# Main.net
KiCad netlist of a schematic drawn in Altium Designer
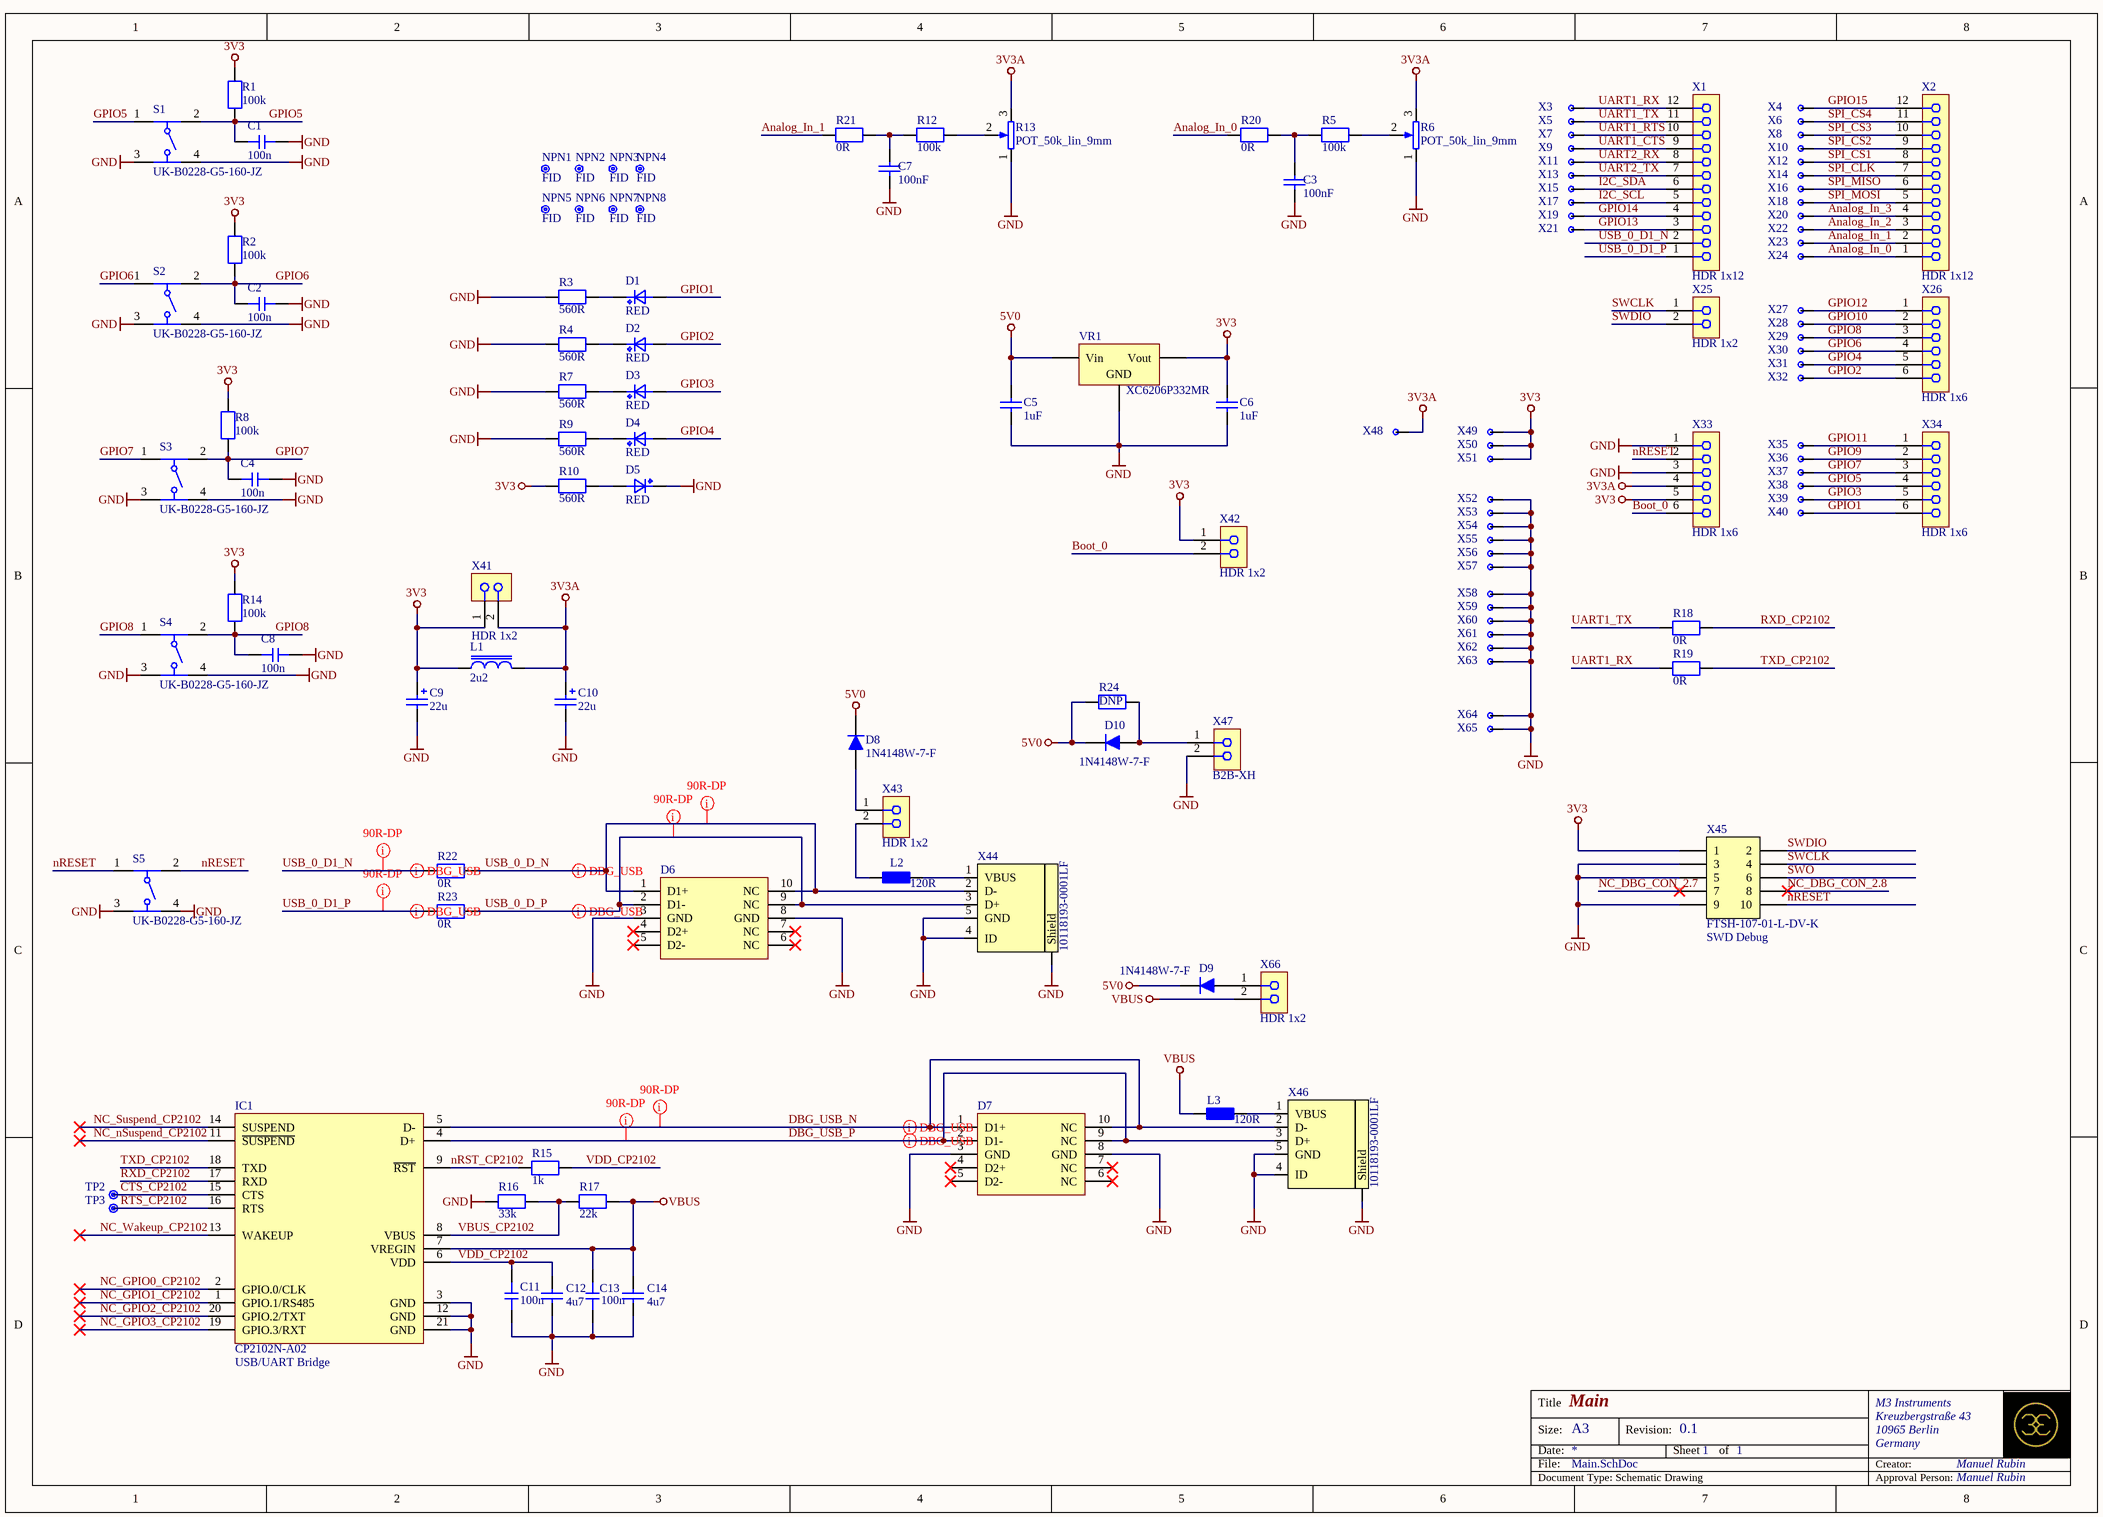
[diagram p0: Main.SchDoc]

(export (version "E")
  (design (tool "Eeschema 10.0.6"))
  (components
    (comp (ref "C1")
      (value "100n")
      (footprint "CAPC1608X95N")
      (description "100n_50V")
      (fields (field (name "MANUFACTURER") "AVX") (field (name "MANUFACTURER PART NUMBER") "06031C104KAT2A"))
      (libsource (lib "Raindancer") (part "C_100n_50V_0603"))
    )
    (comp (ref "C2")
      (value "100n")
      (footprint "CAPC1608X95N")
      (description "100n_50V")
      (fields (field (name "MANUFACTURER") "AVX") (field (name "MANUFACTURER PART NUMBER") "06031C104KAT2A"))
      (libsource (lib "Raindancer") (part "C_100n_50V_0603"))
    )
    (comp (ref "C3")
      (value "100nF")
      (footprint "CAPC1608X95N")
      (description "Multilayer Ceramic Capacitors MLCC - SMD/SMT, 100nF")
      (fields
        (field (name "MANUFACTURER") "YAGEO")
        (field (name "MANUFACTURER PART NUMBER") "CC0603KRX7R9BB104")
      )
      (libsource (lib "Caps") (part "CAP_100nF_0603"))
    )
    (comp (ref "C4")
      (value "100n")
      (footprint "CAPC1608X95N")
      (description "100n_50V")
      (fields (field (name "MANUFACTURER") "AVX") (field (name "MANUFACTURER PART NUMBER") "06031C104KAT2A"))
      (libsource (lib "Raindancer") (part "C_100n_50V_0603"))
    )
    (comp (ref "C5")
      (value "1uF")
      (footprint "CAPC2012X145N")
      (description "Multilayer Ceramic Capacitors MLCC - SMD/SMT, 1uF")
      (fields (field (name "MANUFACTURER") "Samsung Electro-Mechanics") (field (name "TOLERANCE") "10%"))
      (libsource (lib "Caps") (part "CAP_1uF_0805"))
    )
    (comp (ref "C6")
      (value "1uF")
      (footprint "CAPC2012X145N")
      (description "Multilayer Ceramic Capacitors MLCC - SMD/SMT, 1uF")
      (fields (field (name "MANUFACTURER") "Samsung Electro-Mechanics") (field (name "TOLERANCE") "10%"))
      (libsource (lib "Caps") (part "CAP_1uF_0805"))
    )
    (comp (ref "C7")
      (value "100nF")
      (footprint "CAPC1608X95N")
      (description "Multilayer Ceramic Capacitors MLCC - SMD/SMT, 100nF")
      (fields
        (field (name "MANUFACTURER") "YAGEO")
        (field (name "MANUFACTURER PART NUMBER") "CC0603KRX7R9BB104")
      )
      (libsource (lib "Caps") (part "CAP_100nF_0603"))
    )
    (comp (ref "C8")
      (value "100n")
      (footprint "CAPC1608X95N")
      (description "100n_50V")
      (fields (field (name "MANUFACTURER") "AVX") (field (name "MANUFACTURER PART NUMBER") "06031C104KAT2A"))
      (libsource (lib "Raindancer") (part "C_100n_50V_0603"))
    )
    (comp (ref "C9")
      (value "22u")
      (footprint "CAPAE4643X54M")
      (description "Aluminium Electrolytic Capacitors - SMD 22UF 16V HA SMD")
      (fields
        (field (name "MANUFACTURER") "Panasonic")
        (field (name "MANUFACTURER PART NUMBER") "EEE-HAC220WAR")
      )
      (libsource (lib "Caps") (part "CAP_22u"))
    )
    (comp (ref "C10")
      (value "22u")
      (footprint "CAPAE4643X54M")
      (description "Aluminium Electrolytic Capacitors - SMD 22UF 16V HA SMD")
      (fields
        (field (name "MANUFACTURER") "Panasonic")
        (field (name "MANUFACTURER PART NUMBER") "EEE-HAC220WAR")
      )
      (libsource (lib "Caps") (part "CAP_22u"))
    )
    (comp (ref "C11")
      (value "100n")
      (footprint "CAPC1608X95N")
      (description "100n_50V")
      (fields (field (name "MANUFACTURER") "AVX") (field (name "MANUFACTURER PART NUMBER") "06031C104KAT2A"))
      (libsource (lib "Raindancer") (part "C_100n_50V_0603"))
    )
    (comp (ref "C12")
      (value "4u7")
      (footprint "CAPC1608X95N")
      (description "16V 4.7uF X5R ±10% 0603 Multilayer Ceramic Capacitors MLCC - SMD/SMT ROHS")
      (fields
        (field (name "MANUFACTURER") "Murata Electronics")
        (field (name "MANUFACTURER PART NUMBER") "GRM188C81C475KE11D")
      )
      (libsource (lib "Caps") (part "CAP_4u7_0603"))
    )
    (comp (ref "C13")
      (value "100n")
      (footprint "CAPC1608X95N")
      (description "100n_50V")
      (fields (field (name "MANUFACTURER") "AVX") (field (name "MANUFACTURER PART NUMBER") "06031C104KAT2A"))
      (libsource (lib "Raindancer") (part "C_100n_50V_0603"))
    )
    (comp (ref "C14")
      (value "4u7")
      (footprint "CAPC1608X95N")
      (description "16V 4.7uF X5R ±10% 0603 Multilayer Ceramic Capacitors MLCC - SMD/SMT ROHS")
      (fields
        (field (name "MANUFACTURER") "Murata Electronics")
        (field (name "MANUFACTURER PART NUMBER") "GRM188C81C475KE11D")
      )
      (libsource (lib "Caps") (part "CAP_4u7_0603"))
    )
    (comp (ref "D1")
      (value "RED")
      (footprint "WL-SMCW_0805")
      (description "Standard LEDs - SMD WL-SMCW SMDMono TpVw Waterclr 0805 Red")
      (fields
        (field (name "MANUFACTURER") "Wurth Elektronik")
        (field (name "MANUFACTURER PART NUMBER") "150080RS75000")
      )
      (libsource (lib "Diodes") (part "LED_0805_RED_AK"))
    )
    (comp (ref "D2")
      (value "RED")
      (footprint "WL-SMCW_0805")
      (description "Standard LEDs - SMD WL-SMCW SMDMono TpVw Waterclr 0805 Red")
      (fields
        (field (name "MANUFACTURER") "Wurth Elektronik")
        (field (name "MANUFACTURER PART NUMBER") "150080RS75000")
      )
      (libsource (lib "Diodes") (part "LED_0805_RED_AK"))
    )
    (comp (ref "D3")
      (value "RED")
      (footprint "WL-SMCW_0805")
      (description "Standard LEDs - SMD WL-SMCW SMDMono TpVw Waterclr 0805 Red")
      (fields
        (field (name "MANUFACTURER") "Wurth Elektronik")
        (field (name "MANUFACTURER PART NUMBER") "150080RS75000")
      )
      (libsource (lib "Diodes") (part "LED_0805_RED_AK"))
    )
    (comp (ref "D4")
      (value "RED")
      (footprint "WL-SMCW_0805")
      (description "Standard LEDs - SMD WL-SMCW SMDMono TpVw Waterclr 0805 Red")
      (fields
        (field (name "MANUFACTURER") "Wurth Elektronik")
        (field (name "MANUFACTURER PART NUMBER") "150080RS75000")
      )
      (libsource (lib "Diodes") (part "LED_0805_RED_AK"))
    )
    (comp (ref "D5")
      (value "RED")
      (footprint "WL-SMCW_0805")
      (description "Standard LEDs - SMD WL-SMCW SMDMono TpVw Waterclr 0805 Red")
      (fields
        (field (name "MANUFACTURER") "Wurth Elektronik")
        (field (name "MANUFACTURER PART NUMBER") "150080RS75000")
      )
      (libsource (lib "Diodes") (part "LED_0805_RED_AK"))
    )
    (comp (ref "D6")
      (value "~")
      (footprint "DQA R-PUSON-N10")
      (description "2-, 4-Channel ESD Protection for Super-Speed USB 3.0 Interface")
      (fields
        (field (name "MANUFACTURER") "Texas Instruments")
        (field (name "MANUFACTURER PART NUMBER") "TPD4EUSB30DQAR")
      )
      (libsource (lib "Diodes") (part "TPD4EUSB30DQAR"))
    )
    (comp (ref "D7")
      (value "~")
      (footprint "DQA R-PUSON-N10")
      (description "2-, 4-Channel ESD Protection for Super-Speed USB 3.0 Interface")
      (fields
        (field (name "MANUFACTURER") "Texas Instruments")
        (field (name "MANUFACTURER PART NUMBER") "TPD4EUSB30DQAR")
      )
      (libsource (lib "Diodes") (part "TPD4EUSB30DQAR"))
    )
    (comp (ref "D8")
      (value "1N4148W-7-F")
      (footprint "SOD-123")
      (description "Diodes - General Purpose, Power, Switching SURFACE MOUNT FAST SWITCHING DIODE 2A")
      (fields (field (name "MANUFACTURER") "Diodes Incorporated"))
      (libsource (lib "Diodes") (part "1N4148W-7-F"))
    )
    (comp (ref "D9")
      (value "1N4148W-7-F")
      (footprint "SOD-123")
      (description "Diodes - General Purpose, Power, Switching SURFACE MOUNT FAST SWITCHING DIODE 2A")
      (fields (field (name "MANUFACTURER") "Diodes Incorporated"))
      (libsource (lib "Diodes") (part "1N4148W-7-F"))
    )
    (comp (ref "D10")
      (value "1N4148W-7-F")
      (footprint "SOD-123")
      (description "Diodes - General Purpose, Power, Switching SURFACE MOUNT FAST SWITCHING DIODE 2A")
      (fields (field (name "MANUFACTURER") "Diodes Incorporated"))
      (libsource (lib "Diodes") (part "1N4148W-7-F"))
    )
    (comp (ref "IC1")
      (value "CP2102N-A02")
      (footprint "SILABS_CP2102N-A02-GQFN20R")
      (description "USB Interface IC USBXpress - USB to UART Bridge QFN28")
      (fields
        (field (name "MANUFACTURER") "Silicon Labs")
        (field (name "MANUFACTURER PART NUMBER") "CP2102N-A02-GQFN20R")
        (field (name "DEVNOTE") "USB/UART Bridge")
      )
      (libsource (lib "Raindancer") (part "IC_CP2102N-A02-QFN20"))
    )
    (comp (ref "L1")
      (value "2u2")
      (footprint "INDP5050X39N")
      (description "Fixed Inductors 2.2uH 3.8A")
      (fields
        (field (name "MANUFACTURER") "Bourns")
        (field (name "MANUFACTURER PART NUMBER") "SRN5040TA-2R2M")
      )
      (libsource (lib "Inductors") (part "IND_2u2_3.8A"))
    )
    (comp (ref "L2")
      (value "120R")
      (footprint "INDC1608X95AN")
      (description "Chip Bead Inductors for Power Lines")
      (fields
        (field (name "MANUFACTURER") "Taiyo Yuden")
        (field (name "MANUFACTURER PART NUMBER") "FBMH1608HL121-T")
      )
      (libsource (lib "Inductors") (part "FB_600R_0603"))
    )
    (comp (ref "L3")
      (value "120R")
      (footprint "INDC1608X95AN")
      (description "Chip Bead Inductors for Power Lines")
      (fields
        (field (name "MANUFACTURER") "Taiyo Yuden")
        (field (name "MANUFACTURER PART NUMBER") "FBMH1608HL121-T")
      )
      (libsource (lib "Inductors") (part "FB_600R_0603"))
    )
    (comp (ref "NPN1")
      (value "FID")
      (footprint "Fiducial_1mm")
      (libsource (lib "MISC") (part "Fiducial_1mm"))
    )
    (comp (ref "NPN2")
      (value "FID")
      (footprint "Fiducial_1mm")
      (libsource (lib "MISC") (part "Fiducial_1mm"))
    )
    (comp (ref "NPN3")
      (value "FID")
      (footprint "Fiducial_1mm")
      (libsource (lib "MISC") (part "Fiducial_1mm"))
    )
    (comp (ref "NPN4")
      (value "FID")
      (footprint "Fiducial_1mm")
      (libsource (lib "MISC") (part "Fiducial_1mm"))
    )
    (comp (ref "NPN5")
      (value "FID")
      (footprint "Fiducial_1mm")
      (libsource (lib "MISC") (part "Fiducial_1mm"))
    )
    (comp (ref "NPN6")
      (value "FID")
      (footprint "Fiducial_1mm")
      (libsource (lib "MISC") (part "Fiducial_1mm"))
    )
    (comp (ref "NPN7")
      (value "FID")
      (footprint "Fiducial_1mm")
      (libsource (lib "MISC") (part "Fiducial_1mm"))
    )
    (comp (ref "NPN8")
      (value "FID")
      (footprint "Fiducial_1mm")
      (libsource (lib "MISC") (part "Fiducial_1mm"))
    )
    (comp (ref "R1")
      (value "100k")
      (footprint "RESC2012X70N")
      (description "Thick Film Resistors - SMD 1/8watt 100Kohms 1% 100ppm")
      (fields
        (field (name "MANUFACTURER") "Vishay / Dale")
        (field (name "MANUFACTURER PART NUMBER") "CRCW0805100KFKEA")
      )
      (libsource (lib "Resistors") (part "RES_100k_0805"))
    )
    (comp (ref "R2")
      (value "100k")
      (footprint "RESC2012X70N")
      (description "Thick Film Resistors - SMD 1/8watt 100Kohms 1% 100ppm")
      (fields
        (field (name "MANUFACTURER") "Vishay / Dale")
        (field (name "MANUFACTURER PART NUMBER") "CRCW0805100KFKEA")
      )
      (libsource (lib "Resistors") (part "RES_100k_0805"))
    )
    (comp (ref "R3")
      (value "560R")
      (footprint "RESC1608X55N")
      (description "Thick Film Resistors - SMD 560 Ohms 125 mW 0603")
      (fields
        (field (name "MANUFACTURER") "ROHM Semicon")
        (field (name "MANUFACTURER PART NUMBER") "MCR03ERTF5600")
      )
      (libsource (lib "Resistors") (part "RES_560R_0603"))
    )
    (comp (ref "R4")
      (value "560R")
      (footprint "RESC1608X55N")
      (description "Thick Film Resistors - SMD 560 Ohms 125 mW 0603")
      (fields
        (field (name "MANUFACTURER") "ROHM Semicon")
        (field (name "MANUFACTURER PART NUMBER") "MCR03ERTF5600")
      )
      (libsource (lib "Resistors") (part "RES_560R_0603"))
    )
    (comp (ref "R5")
      (value "100k")
      (footprint "RESC2012X70N")
      (description "Thick Film Resistors - SMD 1/8watt 100Kohms 1% 100ppm")
      (fields
        (field (name "MANUFACTURER") "Vishay / Dale")
        (field (name "MANUFACTURER PART NUMBER") "CRCW0805100KFKEA")
      )
      (libsource (lib "") (part "RES_100k_0805_1"))
    )
    (comp (ref "R6")
      (value "POT_50k_lin_9mm")
      (footprint "PTV09")
      (description "PTV09A-4020F-A203 50k, 20mm")
      (fields
        (field (name "MANUFACTURER") "Bourns")
        (field (name "MANUFACTURER PART NUMBER") "PTV09A-5020F-A503")
      )
      (libsource (lib "Resistors") (part "POT_50k_lin_9mm"))
    )
    (comp (ref "R7")
      (value "560R")
      (footprint "RESC1608X55N")
      (description "Thick Film Resistors - SMD 560 Ohms 125 mW 0603")
      (fields
        (field (name "MANUFACTURER") "ROHM Semicon")
        (field (name "MANUFACTURER PART NUMBER") "MCR03ERTF5600")
      )
      (libsource (lib "Resistors") (part "RES_560R_0603"))
    )
    (comp (ref "R8")
      (value "100k")
      (footprint "RESC2012X70N")
      (description "Thick Film Resistors - SMD 1/8watt 100Kohms 1% 100ppm")
      (fields
        (field (name "MANUFACTURER") "Vishay / Dale")
        (field (name "MANUFACTURER PART NUMBER") "CRCW0805100KFKEA")
      )
      (libsource (lib "Resistors") (part "RES_100k_0805"))
    )
    (comp (ref "R9")
      (value "560R")
      (footprint "RESC1608X55N")
      (description "Thick Film Resistors - SMD 560 Ohms 125 mW 0603")
      (fields
        (field (name "MANUFACTURER") "ROHM Semicon")
        (field (name "MANUFACTURER PART NUMBER") "MCR03ERTF5600")
      )
      (libsource (lib "Resistors") (part "RES_560R_0603"))
    )
    (comp (ref "R10")
      (value "560R")
      (footprint "RESC1608X55N")
      (description "Thick Film Resistors - SMD 560 Ohms 125 mW 0603")
      (fields
        (field (name "MANUFACTURER") "ROHM Semicon")
        (field (name "MANUFACTURER PART NUMBER") "MCR03ERTF5600")
      )
      (libsource (lib "Resistors") (part "RES_560R_0603"))
    )
    (comp (ref "R12")
      (value "100k")
      (footprint "RESC2012X70N")
      (description "Thick Film Resistors - SMD 1/8watt 100Kohms 1% 100ppm")
      (fields
        (field (name "MANUFACTURER") "Vishay / Dale")
        (field (name "MANUFACTURER PART NUMBER") "CRCW0805100KFKEA")
      )
      (libsource (lib "") (part "RES_100k_0805_1"))
    )
    (comp (ref "R13")
      (value "POT_50k_lin_9mm")
      (footprint "PTV09")
      (description "PTV09A-4020F-A203 50k, 20mm")
      (fields
        (field (name "MANUFACTURER") "Bourns")
        (field (name "MANUFACTURER PART NUMBER") "PTV09A-5020F-A503")
      )
      (libsource (lib "Resistors") (part "POT_50k_lin_9mm"))
    )
    (comp (ref "R14")
      (value "100k")
      (footprint "RESC2012X70N")
      (description "Thick Film Resistors - SMD 1/8watt 100Kohms 1% 100ppm")
      (fields
        (field (name "MANUFACTURER") "Vishay / Dale")
        (field (name "MANUFACTURER PART NUMBER") "CRCW0805100KFKEA")
      )
      (libsource (lib "Resistors") (part "RES_100k_0805"))
    )
    (comp (ref "R15")
      (value "1k")
      (footprint "RESC1608X55AN")
      (description "Thick Film Resistors - SMD 1 kOhms 100mW 0603 1%")
      (fields
        (field (name "MANUFACTURER") "Yageo")
        (field (name "MANUFACTURER PART NUMBER") "RC0603FR-071KL")
      )
      (libsource (lib "Raindancer") (part "RES_1k_0603"))
    )
    (comp (ref "R16")
      (value "33k")
      (footprint "RESC1608X55AN")
      (description "Thick Film Resistors - SMD 33 kOhms 100 mW 0603 5%")
      (fields
        (field (name "MANUFACTURER") "YAGEO")
        (field (name "MANUFACTURER PART NUMBER") "RC0603JR-0733KL")
      )
      (libsource (lib "Raindancer") (part "RES_33k_0603"))
    )
    (comp (ref "R17")
      (value "22k")
      (footprint "RESC1608X55AN")
      (description "Thick Film Resistors - SMD 22kOhms 1/10W 0603 1%")
      (fields
        (field (name "MANUFACTURER") "YAGEO")
        (field (name "MANUFACTURER PART NUMBER") "RC0603FR-7W22KL")
      )
      (libsource (lib "Raindancer") (part "RES_22k_0603"))
    )
    (comp (ref "R18")
      (value "0R")
      (footprint "RESC1608X55N")
      (description "Thick Film Resistors - SMD 1/10watt ZEROohm Jumper")
      (fields
        (field (name "MANUFACTURER") "Vishay")
        (field (name "MANUFACTURER PART NUMBER") "CRCW06030000Z0EA")
      )
      (libsource (lib "Resistors") (part "RES_0R_0603"))
    )
    (comp (ref "R19")
      (value "0R")
      (footprint "RESC1608X55N")
      (description "Thick Film Resistors - SMD 1/10watt ZEROohm Jumper")
      (fields
        (field (name "MANUFACTURER") "Vishay")
        (field (name "MANUFACTURER PART NUMBER") "CRCW06030000Z0EA")
      )
      (libsource (lib "Resistors") (part "RES_0R_0603"))
    )
    (comp (ref "R20")
      (value "0R")
      (footprint "RESC1608X55N")
      (description "Thick Film Resistors - SMD 1/10watt ZEROohm Jumper")
      (fields
        (field (name "MANUFACTURER") "Vishay")
        (field (name "MANUFACTURER PART NUMBER") "CRCW06030000Z0EA")
      )
      (libsource (lib "Resistors") (part "RES_0R_0603"))
    )
    (comp (ref "R21")
      (value "0R")
      (footprint "RESC1608X55N")
      (description "Thick Film Resistors - SMD 1/10watt ZEROohm Jumper")
      (fields
        (field (name "MANUFACTURER") "Vishay")
        (field (name "MANUFACTURER PART NUMBER") "CRCW06030000Z0EA")
      )
      (libsource (lib "Resistors") (part "RES_0R_0603"))
    )
    (comp (ref "R22")
      (value "0R")
      (footprint "RESC1608X55N")
      (description "Thick Film Resistors - SMD 1/10watt ZEROohm Jumper")
      (fields
        (field (name "MANUFACTURER") "Vishay")
        (field (name "MANUFACTURER PART NUMBER") "CRCW06030000Z0EA")
      )
      (libsource (lib "Resistors") (part "RES_0R_0603"))
    )
    (comp (ref "R23")
      (value "0R")
      (footprint "RESC1608X55N")
      (description "Thick Film Resistors - SMD 1/10watt ZEROohm Jumper")
      (fields
        (field (name "MANUFACTURER") "Vishay")
        (field (name "MANUFACTURER PART NUMBER") "CRCW06030000Z0EA")
      )
      (libsource (lib "Resistors") (part "RES_0R_0603"))
    )
    (comp (ref "R24")
      (value "DNP")
      (footprint "RESC2012X70N")
      (description "Resistor SMD 0805 - not populated")
      (libsource (lib "Resistors") (part "RES_DNF_0805"))
    )
    (comp (ref "S1")
      (value "UK-B0228-G5-160-JZ")
      (footprint "UK-B0228-G5-160-JZ")
      (fields (field (name "MANUFACTURER") "USAKRO"))
      (libsource (lib "Switches") (part "SW_UK-B0228-G5-160-JZ"))
    )
    (comp (ref "S2")
      (value "UK-B0228-G5-160-JZ")
      (footprint "UK-B0228-G5-160-JZ")
      (fields (field (name "MANUFACTURER") "USAKRO"))
      (libsource (lib "Switches") (part "SW_UK-B0228-G5-160-JZ"))
    )
    (comp (ref "S3")
      (value "UK-B0228-G5-160-JZ")
      (footprint "UK-B0228-G5-160-JZ")
      (fields (field (name "MANUFACTURER") "USAKRO"))
      (libsource (lib "Switches") (part "SW_UK-B0228-G5-160-JZ"))
    )
    (comp (ref "S4")
      (value "UK-B0228-G5-160-JZ")
      (footprint "UK-B0228-G5-160-JZ")
      (fields (field (name "MANUFACTURER") "USAKRO"))
      (libsource (lib "Switches") (part "SW_UK-B0228-G5-160-JZ"))
    )
    (comp (ref "S5")
      (value "UK-B0228-G5-160-JZ")
      (footprint "UK-B0228-G5-160-JZ")
      (fields (field (name "MANUFACTURER") "USAKRO"))
      (libsource (lib "Switches") (part "SW_UK-B0228-G5-160-JZ"))
    )
    (comp (ref "TP2")
      (value "TP 0.7mm")
      (footprint "TP_0.7mm")
      (description "Test Pad surface mount")
      (libsource (lib "Raindancer") (part "MISC_Test Pad 0.7mm"))
    )
    (comp (ref "TP3")
      (value "TP 0.7mm")
      (footprint "TP_0.7mm")
      (description "Test Pad surface mount")
      (libsource (lib "Raindancer") (part "MISC_Test Pad 0.7mm"))
    )
    (comp (ref "VR1")
      (value "XC6206P332MR")
      (footprint "SOT95P280X135-3N_123")
      (description "LOW DROPOUT REGULATORS(LDO) POSITIVE FIXED 680MV @ 100MA 6V 3.3V 200MA SOT-23-3L ROHS")
      (fields (field (name "MANUFACTURER") "Torex Semicon"))
      (libsource (lib "ICs") (part "IC_XC6206P332MR"))
    )
    (comp (ref "X1")
      (value "HDR 1x12")
      (footprint "61301211821_NO")
      (description "Board-to-Board-Steckverbinder, 2.54 mm, 12 Kontakt(e), Stiftleiste 1-Reihig")
      (fields (field (name "MANUFACTURER") "WE") (field (name "MANUFACTURER PART NUMBER") "61301211821"))
      (libsource (lib "Connectors") (part "CON_HEADER_1X12_FEMALE_NO"))
    )
    (comp (ref "X2")
      (value "HDR 1x12")
      (footprint "61301211821_NO")
      (description "Board-to-Board-Steckverbinder, 2.54 mm, 12 Kontakt(e), Stiftleiste 1-Reihig")
      (fields (field (name "MANUFACTURER") "WE") (field (name "MANUFACTURER PART NUMBER") "61301211821"))
      (libsource (lib "Connectors") (part "CON_HEADER_1X12_FEMALE_NO"))
    )
    (comp (ref "X3") (value "PAD") (footprint "PAD_1.1_1.6") (libsource (lib "MISC") (part "PAD_2.54")))
    (comp (ref "X4") (value "PAD") (footprint "PAD_1.1_1.6") (libsource (lib "MISC") (part "PAD_2.54")))
    (comp (ref "X5") (value "PAD") (footprint "PAD_1.1_1.6") (libsource (lib "MISC") (part "PAD_2.54")))
    (comp (ref "X6") (value "PAD") (footprint "PAD_1.1_1.6") (libsource (lib "MISC") (part "PAD_2.54")))
    (comp (ref "X7") (value "PAD") (footprint "PAD_1.1_1.6") (libsource (lib "MISC") (part "PAD_2.54")))
    (comp (ref "X8") (value "PAD") (footprint "PAD_1.1_1.6") (libsource (lib "MISC") (part "PAD_2.54")))
    (comp (ref "X9") (value "PAD") (footprint "PAD_1.1_1.6") (libsource (lib "MISC") (part "PAD_2.54")))
    (comp (ref "X10") (value "PAD") (footprint "PAD_1.1_1.6") (libsource (lib "MISC") (part "PAD_2.54")))
    (comp (ref "X11") (value "PAD") (footprint "PAD_1.1_1.6") (libsource (lib "MISC") (part "PAD_2.54")))
    (comp (ref "X12") (value "PAD") (footprint "PAD_1.1_1.6") (libsource (lib "MISC") (part "PAD_2.54")))
    (comp (ref "X13") (value "PAD") (footprint "PAD_1.1_1.6") (libsource (lib "MISC") (part "PAD_2.54")))
    (comp (ref "X14") (value "PAD") (footprint "PAD_1.1_1.6") (libsource (lib "MISC") (part "PAD_2.54")))
    (comp (ref "X15") (value "PAD") (footprint "PAD_1.1_1.6") (libsource (lib "MISC") (part "PAD_2.54")))
    (comp (ref "X16") (value "PAD") (footprint "PAD_1.1_1.6") (libsource (lib "MISC") (part "PAD_2.54")))
    (comp (ref "X17") (value "PAD") (footprint "PAD_1.1_1.6") (libsource (lib "MISC") (part "PAD_2.54")))
    (comp (ref "X18") (value "PAD") (footprint "PAD_1.1_1.6") (libsource (lib "MISC") (part "PAD_2.54")))
    (comp (ref "X19") (value "PAD") (footprint "PAD_1.1_1.6") (libsource (lib "MISC") (part "PAD_2.54")))
    (comp (ref "X20") (value "PAD") (footprint "PAD_1.1_1.6") (libsource (lib "MISC") (part "PAD_2.54")))
    (comp (ref "X21") (value "PAD") (footprint "PAD_1.1_1.6") (libsource (lib "MISC") (part "PAD_2.54")))
    (comp (ref "X22") (value "PAD") (footprint "PAD_1.1_1.6") (libsource (lib "MISC") (part "PAD_2.54")))
    (comp (ref "X23") (value "PAD") (footprint "PAD_1.1_1.6") (libsource (lib "MISC") (part "PAD_2.54")))
    (comp (ref "X24") (value "PAD") (footprint "PAD_1.1_1.6") (libsource (lib "MISC") (part "PAD_2.54")))
    (comp (ref "X25")
      (value "HDR 1x2")
      (footprint "61300211821_NO")
      (description "Board-to-Board-Steckverbinder, 2.54 mm, 2 Kontakt(e), Stiftleiste 1-Reihig")
      (fields (field (name "MANUFACTURER") "WE") (field (name "MANUFACTURER PART NUMBER") "61300211821"))
      (libsource (lib "Connectors") (part "CON_HEADER_1X2_FEMALE_NO"))
    )
    (comp (ref "X26")
      (value "HDR 1x6")
      (footprint "61300611821_NO")
      (description "Board-to-Board-Steckverbinder, 2.54 mm, 6 Kontakt(e), Stiftleiste 1-Reihig")
      (fields (field (name "MANUFACTURER") "WE") (field (name "MANUFACTURER PART NUMBER") "61300611821"))
      (libsource (lib "Connectors") (part "CON_HEADER_1X6_FEMALE_NO"))
    )
    (comp (ref "X27") (value "PAD") (footprint "PAD_1.1_1.6") (libsource (lib "MISC") (part "PAD_2.54")))
    (comp (ref "X28") (value "PAD") (footprint "PAD_1.1_1.6") (libsource (lib "MISC") (part "PAD_2.54")))
    (comp (ref "X29") (value "PAD") (footprint "PAD_1.1_1.6") (libsource (lib "MISC") (part "PAD_2.54")))
    (comp (ref "X30") (value "PAD") (footprint "PAD_1.1_1.6") (libsource (lib "MISC") (part "PAD_2.54")))
    (comp (ref "X31") (value "PAD") (footprint "PAD_1.1_1.6") (libsource (lib "MISC") (part "PAD_2.54")))
    (comp (ref "X32") (value "PAD") (footprint "PAD_1.1_1.6") (libsource (lib "MISC") (part "PAD_2.54")))
    (comp (ref "X33")
      (value "HDR 1x6")
      (footprint "61300611821_NO")
      (description "Board-to-Board-Steckverbinder, 2.54 mm, 6 Kontakt(e), Stiftleiste 1-Reihig")
      (fields (field (name "MANUFACTURER") "WE") (field (name "MANUFACTURER PART NUMBER") "61300611821"))
      (libsource (lib "Connectors") (part "CON_HEADER_1X6_FEMALE_NO"))
    )
    (comp (ref "X34")
      (value "HDR 1x6")
      (footprint "61300611821_NO")
      (description "Board-to-Board-Steckverbinder, 2.54 mm, 6 Kontakt(e), Stiftleiste 1-Reihig")
      (fields (field (name "MANUFACTURER") "WE") (field (name "MANUFACTURER PART NUMBER") "61300611821"))
      (libsource (lib "Connectors") (part "CON_HEADER_1X6_FEMALE_NO"))
    )
    (comp (ref "X35") (value "PAD") (footprint "PAD_1.1_1.6") (libsource (lib "MISC") (part "PAD_2.54")))
    (comp (ref "X36") (value "PAD") (footprint "PAD_1.1_1.6") (libsource (lib "MISC") (part "PAD_2.54")))
    (comp (ref "X37") (value "PAD") (footprint "PAD_1.1_1.6") (libsource (lib "MISC") (part "PAD_2.54")))
    (comp (ref "X38") (value "PAD") (footprint "PAD_1.1_1.6") (libsource (lib "MISC") (part "PAD_2.54")))
    (comp (ref "X39") (value "PAD") (footprint "PAD_1.1_1.6") (libsource (lib "MISC") (part "PAD_2.54")))
    (comp (ref "X40") (value "PAD") (footprint "PAD_1.1_1.6") (libsource (lib "MISC") (part "PAD_2.54")))
    (comp (ref "X41")
      (value "HDR 1x2")
      (footprint "CON_HEADER2.54_1x2W")
      (description "Board-to-Board-Steckverbinder, 2.54 mm, 2 Kontakt(e), Stiftleiste 1-Reihig")
      (fields
        (field (name "MANUFACTURER") "Samtec")
        (field (name "MANUFACTURER PART NUMBER") "TSW-102-07-T-S")
      )
      (libsource (lib "") (part "CON_HEADER_1X2_1"))
    )
    (comp (ref "X42")
      (value "HDR 1x2")
      (footprint "CON_HEADER2.54_1x2W")
      (description "Board-to-Board-Steckverbinder, 2.54 mm, 2 Kontakt(e), Stiftleiste 1-Reihig")
      (fields
        (field (name "MANUFACTURER") "Samtec")
        (field (name "MANUFACTURER PART NUMBER") "TSW-102-07-T-S")
      )
      (libsource (lib "Connectors") (part "CON_HEADER_1X2"))
    )
    (comp (ref "X43")
      (value "HDR 1x2")
      (footprint "CON_HEADER2.54_1x2W")
      (description "Board-to-Board-Steckverbinder, 2.54 mm, 2 Kontakt(e), Stiftleiste 1-Reihig")
      (fields
        (field (name "MANUFACTURER") "Samtec")
        (field (name "MANUFACTURER PART NUMBER") "TSW-102-07-T-S")
      )
      (libsource (lib "Connectors") (part "CON_HEADER_1X2"))
    )
    (comp (ref "X44")
      (value "10118193-0001LF")
      (footprint "USB-Micro-B-RA-SMD-PiP")
      (description "MicroUSB-B-SMT")
      (fields (field (name "MANUFACTURER") "Amphenol ICC (FCI)"))
      (libsource (lib "Connectors") (part "CON_MiniUSB-AB-SMT"))
    )
    (comp (ref "X45")
      (value "FTSH-107-01-L-DV-K")
      (footprint "HDR_2x5-SMD-1.27mm-K")
      (description "Pin Header 2x5, 1.27mm (50mil), SMD, Keying Shroud")
      (fields
        (field (name "MANUFACTURER") "Samtec")
        (field (name "MANUFACTURER PART NUMBER") "FTSH-105-01-L-DV-K")
        (field (name "DEVNOTE") "SWD Debug")
      )
      (libsource (lib "Raindancer") (part "CON_2x5_SMD_1.27mm"))
    )
    (comp (ref "X46")
      (value "10118193-0001LF")
      (footprint "USB-Micro-B-RA-SMD-PiP")
      (description "MicroUSB-B-SMT")
      (fields (field (name "MANUFACTURER") "Amphenol ICC (FCI)"))
      (libsource (lib "Connectors") (part "CON_MiniUSB-AB-SMT"))
    )
    (comp (ref "X47")
      (value "B2B-XH")
      (footprint "JST_B2B-XH-A_(LF)(SN)")
      (description "Connector Header Through Hole 2 position 0.098\" (2.50mm)")
      (fields
        (field (name "MANUFACTURER") "JST")
        (field (name "MANUFACTURER PART NUMBER") "B2B-XH-A (LF)(SN)")
      )
      (libsource (lib "Connectors") (part "CON_JST_B2B-XH"))
    )
    (comp (ref "X48") (value "PAD") (footprint "PAD_1.1_1.6") (libsource (lib "MISC") (part "PAD_2.54")))
    (comp (ref "X49") (value "PAD") (footprint "PAD_1.1_1.6") (libsource (lib "MISC") (part "PAD_2.54")))
    (comp (ref "X50") (value "PAD") (footprint "PAD_1.1_1.6") (libsource (lib "MISC") (part "PAD_2.54")))
    (comp (ref "X51") (value "PAD") (footprint "PAD_1.1_1.6") (libsource (lib "MISC") (part "PAD_2.54")))
    (comp (ref "X52") (value "PAD") (footprint "PAD_1.1_1.6") (libsource (lib "MISC") (part "PAD_2.54")))
    (comp (ref "X53") (value "PAD") (footprint "PAD_1.1_1.6") (libsource (lib "MISC") (part "PAD_2.54")))
    (comp (ref "X54") (value "PAD") (footprint "PAD_1.1_1.6") (libsource (lib "MISC") (part "PAD_2.54")))
    (comp (ref "X55") (value "PAD") (footprint "PAD_1.1_1.6") (libsource (lib "MISC") (part "PAD_2.54")))
    (comp (ref "X56") (value "PAD") (footprint "PAD_1.1_1.6") (libsource (lib "MISC") (part "PAD_2.54")))
    (comp (ref "X57") (value "PAD") (footprint "PAD_1.1_1.6") (libsource (lib "MISC") (part "PAD_2.54")))
    (comp (ref "X58") (value "PAD") (footprint "PAD_1.1_1.6") (libsource (lib "MISC") (part "PAD_2.54")))
    (comp (ref "X59") (value "PAD") (footprint "PAD_1.1_1.6") (libsource (lib "MISC") (part "PAD_2.54")))
    (comp (ref "X60") (value "PAD") (footprint "PAD_1.1_1.6") (libsource (lib "MISC") (part "PAD_2.54")))
    (comp (ref "X61") (value "PAD") (footprint "PAD_1.1_1.6") (libsource (lib "MISC") (part "PAD_2.54")))
    (comp (ref "X62") (value "PAD") (footprint "PAD_1.1_1.6") (libsource (lib "MISC") (part "PAD_2.54")))
    (comp (ref "X63") (value "PAD") (footprint "PAD_1.1_1.6") (libsource (lib "MISC") (part "PAD_2.54")))
    (comp (ref "X64") (value "PAD") (footprint "PAD_1.1_1.6") (libsource (lib "MISC") (part "PAD_2.54")))
    (comp (ref "X65") (value "PAD") (footprint "PAD_1.1_1.6") (libsource (lib "MISC") (part "PAD_2.54")))
    (comp (ref "X66")
      (value "HDR 1x2")
      (footprint "CON_HEADER2.54_1x2W")
      (description "Board-to-Board-Steckverbinder, 2.54 mm, 2 Kontakt(e), Stiftleiste 1-Reihig")
      (fields
        (field (name "MANUFACTURER") "Samtec")
        (field (name "MANUFACTURER PART NUMBER") "TSW-102-07-T-S")
      )
      (libsource (lib "Connectors") (part "CON_HEADER_1X2"))
    )
  )
  (nets
    (net (code "1") (name "/Analog_In_0") (class "Default")
      (node (ref "R20") (pin "2") (pinfunction "2_2") (pintype "passive"))
      (node (ref "X2") (pin "1") (pinfunction "1_1") (pintype "passive"))
      (node (ref "X24") (pin "1") (pinfunction "1_1") (pintype "passive"))
    )
    (net (code "2") (name "/Analog_In_1") (class "Default")
      (node (ref "R21") (pin "2") (pinfunction "2_2") (pintype "passive"))
      (node (ref "X2") (pin "2") (pinfunction "2_2") (pintype "passive"))
      (node (ref "X23") (pin "1") (pinfunction "1_1") (pintype "passive"))
    )
    (net (code "3") (name "/Analog_In_2") (class "Default")
      (node (ref "X2") (pin "3") (pinfunction "3_3") (pintype "passive"))
      (node (ref "X22") (pin "1") (pinfunction "1_1") (pintype "passive"))
    )
    (net (code "4") (name "/Analog_In_3") (class "Default")
      (node (ref "X2") (pin "4") (pinfunction "4_4") (pintype "passive"))
      (node (ref "X20") (pin "1") (pinfunction "1_1") (pintype "passive"))
    )
    (net (code "5") (name "/Boot_0") (class "Default")
      (node (ref "X33") (pin "6") (pinfunction "6_6") (pintype "passive"))
      (node (ref "X42") (pin "2") (pinfunction "2_2") (pintype "passive"))
    )
    (net (code "6") (name "/CTS_CP2102") (class "Default")
      (node (ref "IC1") (pin "15") (pinfunction "CTS_15") (pintype "passive"))
      (node (ref "TP2") (pin "1") (pinfunction "1_1") (pintype "passive"))
    )
    (net (code "7") (name "/DBG_USB_N") (class "Default")
      (node (ref "D7") (pin "1") (pinfunction "D1+_1") (pintype "passive"))
      (node (ref "D7") (pin "10") (pinfunction "NC_10") (pintype "passive"))
      (node (ref "IC1") (pin "5") (pinfunction "D-_5") (pintype "passive"))
      (node (ref "X46") (pin "2") (pinfunction "D-_2") (pintype "passive"))
    )
    (net (code "8") (name "/DBG_USB_P") (class "Default")
      (node (ref "D7") (pin "2") (pinfunction "D1-_2") (pintype "passive"))
      (node (ref "D7") (pin "9") (pinfunction "NC_9") (pintype "passive"))
      (node (ref "IC1") (pin "4") (pinfunction "D+_4") (pintype "passive"))
      (node (ref "X46") (pin "3") (pinfunction "D+_3") (pintype "passive"))
    )
    (net (code "9") (name "/GPIO1") (class "Default")
      (node (ref "D1") (pin "A") (pinfunction "A_A") (pintype "passive"))
      (node (ref "X34") (pin "6") (pinfunction "6_6") (pintype "passive"))
      (node (ref "X40") (pin "1") (pinfunction "1_1") (pintype "passive"))
    )
    (net (code "10") (name "/GPIO2") (class "Default")
      (node (ref "D2") (pin "A") (pinfunction "A_A") (pintype "passive"))
      (node (ref "X26") (pin "6") (pinfunction "6_6") (pintype "passive"))
      (node (ref "X32") (pin "1") (pinfunction "1_1") (pintype "passive"))
    )
    (net (code "11") (name "/GPIO3") (class "Default")
      (node (ref "D3") (pin "A") (pinfunction "A_A") (pintype "passive"))
      (node (ref "X34") (pin "5") (pinfunction "5_5") (pintype "passive"))
      (node (ref "X39") (pin "1") (pinfunction "1_1") (pintype "passive"))
    )
    (net (code "12") (name "/GPIO4") (class "Default")
      (node (ref "D4") (pin "A") (pinfunction "A_A") (pintype "passive"))
      (node (ref "X26") (pin "5") (pinfunction "5_5") (pintype "passive"))
      (node (ref "X31") (pin "1") (pinfunction "1_1") (pintype "passive"))
    )
    (net (code "13") (name "/GPIO5") (class "Default")
      (node (ref "C1") (pin "1") (pinfunction "1_1") (pintype "passive"))
      (node (ref "R1") (pin "1") (pinfunction "1_1") (pintype "passive"))
      (node (ref "S1") (pin "1") (pinfunction "1_1") (pintype "passive"))
      (node (ref "S1") (pin "2") (pinfunction "2_2") (pintype "passive"))
      (node (ref "X34") (pin "4") (pinfunction "4_4") (pintype "passive"))
      (node (ref "X38") (pin "1") (pinfunction "1_1") (pintype "passive"))
    )
    (net (code "14") (name "/GPIO6") (class "Default")
      (node (ref "C2") (pin "1") (pinfunction "1_1") (pintype "passive"))
      (node (ref "R2") (pin "1") (pinfunction "1_1") (pintype "passive"))
      (node (ref "S2") (pin "1") (pinfunction "1_1") (pintype "passive"))
      (node (ref "S2") (pin "2") (pinfunction "2_2") (pintype "passive"))
      (node (ref "X26") (pin "4") (pinfunction "4_4") (pintype "passive"))
      (node (ref "X30") (pin "1") (pinfunction "1_1") (pintype "passive"))
    )
    (net (code "15") (name "/GPIO7") (class "Default")
      (node (ref "C4") (pin "1") (pinfunction "1_1") (pintype "passive"))
      (node (ref "R8") (pin "1") (pinfunction "1_1") (pintype "passive"))
      (node (ref "S3") (pin "1") (pinfunction "1_1") (pintype "passive"))
      (node (ref "S3") (pin "2") (pinfunction "2_2") (pintype "passive"))
      (node (ref "X34") (pin "3") (pinfunction "3_3") (pintype "passive"))
      (node (ref "X37") (pin "1") (pinfunction "1_1") (pintype "passive"))
    )
    (net (code "16") (name "/GPIO8") (class "Default")
      (node (ref "C8") (pin "1") (pinfunction "1_1") (pintype "passive"))
      (node (ref "R14") (pin "1") (pinfunction "1_1") (pintype "passive"))
      (node (ref "S4") (pin "1") (pinfunction "1_1") (pintype "passive"))
      (node (ref "S4") (pin "2") (pinfunction "2_2") (pintype "passive"))
      (node (ref "X26") (pin "3") (pinfunction "3_3") (pintype "passive"))
      (node (ref "X29") (pin "1") (pinfunction "1_1") (pintype "passive"))
    )
    (net (code "17") (name "/GPIO9") (class "Default")
      (node (ref "X34") (pin "2") (pinfunction "2_2") (pintype "passive"))
      (node (ref "X36") (pin "1") (pinfunction "1_1") (pintype "passive"))
    )
    (net (code "18") (name "/GPIO10") (class "Default")
      (node (ref "X26") (pin "2") (pinfunction "2_2") (pintype "passive"))
      (node (ref "X28") (pin "1") (pinfunction "1_1") (pintype "passive"))
    )
    (net (code "19") (name "/GPIO11") (class "Default")
      (node (ref "X34") (pin "1") (pinfunction "1_1") (pintype "passive"))
      (node (ref "X35") (pin "1") (pinfunction "1_1") (pintype "passive"))
    )
    (net (code "20") (name "/GPIO12") (class "Default")
      (node (ref "X26") (pin "1") (pinfunction "1_1") (pintype "passive"))
      (node (ref "X27") (pin "1") (pinfunction "1_1") (pintype "passive"))
    )
    (net (code "21") (name "/GPIO13") (class "Default")
      (node (ref "X1") (pin "3") (pinfunction "3_3") (pintype "passive"))
      (node (ref "X21") (pin "1") (pinfunction "1_1") (pintype "passive"))
    )
    (net (code "22") (name "/GPIO14") (class "Default")
      (node (ref "X1") (pin "4") (pinfunction "4_4") (pintype "passive"))
      (node (ref "X19") (pin "1") (pinfunction "1_1") (pintype "passive"))
    )
    (net (code "23") (name "/GPIO15") (class "Default")
      (node (ref "X2") (pin "12") (pinfunction "12_12") (pintype "passive"))
      (node (ref "X4") (pin "1") (pinfunction "1_1") (pintype "passive"))
    )
    (net (code "24") (name "/I2C_SCL") (class "Default")
      (node (ref "X1") (pin "5") (pinfunction "5_5") (pintype "passive"))
      (node (ref "X17") (pin "1") (pinfunction "1_1") (pintype "passive"))
    )
    (net (code "25") (name "/I2C_SDA") (class "Default")
      (node (ref "X1") (pin "6") (pinfunction "6_6") (pintype "passive"))
      (node (ref "X15") (pin "1") (pinfunction "1_1") (pintype "passive"))
    )
    (net (code "26") (name "/NC_DBG_CON_2.7") (class "Default")
      (node (ref "X45") (pin "7") (pinfunction "7_7") (pintype "passive+no_connect"))
    )
    (net (code "27") (name "/NC_DBG_CON_2.8") (class "Default")
      (node (ref "X45") (pin "8") (pinfunction "8_8") (pintype "passive+no_connect"))
    )
    (net (code "28") (name "/NC_GPIO0_CP2102") (class "Default")
      (node (ref "IC1") (pin "2") (pinfunction "GPIO.0/CLK_2") (pintype "passive+no_connect"))
    )
    (net (code "29") (name "/NC_GPIO1_CP2102") (class "Default")
      (node (ref "IC1") (pin "1") (pinfunction "GPIO.1/RS485_1") (pintype "passive+no_connect"))
    )
    (net (code "30") (name "/NC_GPIO2_CP2102") (class "Default")
      (node (ref "IC1") (pin "20") (pinfunction "GPIO.2/TXT_20") (pintype "passive+no_connect"))
    )
    (net (code "31") (name "/NC_GPIO3_CP2102") (class "Default")
      (node (ref "IC1") (pin "19") (pinfunction "GPIO.3/RXT_19") (pintype "passive+no_connect"))
    )
    (net (code "32") (name "/NC_Suspend_CP2102") (class "Default")
      (node (ref "IC1") (pin "14") (pinfunction "SUSPEND_14") (pintype "passive+no_connect"))
    )
    (net (code "33") (name "/NC_Wakeup_CP2102") (class "Default")
      (node (ref "IC1") (pin "13") (pinfunction "WAKEUP_13") (pintype "passive+no_connect"))
    )
    (net (code "34") (name "/NC_nSuspend_CP2102") (class "Default")
      (node (ref "IC1") (pin "11") (pinfunction "~{SUSPEND}_11") (pintype "passive+no_connect"))
    )
    (net (code "35") (name "/RTS_CP2102") (class "Default")
      (node (ref "IC1") (pin "16") (pinfunction "RTS_16") (pintype "passive"))
      (node (ref "TP3") (pin "1") (pinfunction "1_1") (pintype "passive"))
    )
    (net (code "36") (name "/RXD_CP2102") (class "Default")
      (node (ref "IC1") (pin "17") (pinfunction "RXD_17") (pintype "passive"))
      (node (ref "R18") (pin "1") (pinfunction "1_1") (pintype "passive"))
    )
    (net (code "37") (name "/SPI_CLK") (class "Default")
      (node (ref "X14") (pin "1") (pinfunction "1_1") (pintype "passive"))
      (node (ref "X2") (pin "7") (pinfunction "7_7") (pintype "passive"))
    )
    (net (code "38") (name "/SPI_CS1") (class "Default")
      (node (ref "X12") (pin "1") (pinfunction "1_1") (pintype "passive"))
      (node (ref "X2") (pin "8") (pinfunction "8_8") (pintype "passive"))
    )
    (net (code "39") (name "/SPI_CS2") (class "Default")
      (node (ref "X10") (pin "1") (pinfunction "1_1") (pintype "passive"))
      (node (ref "X2") (pin "9") (pinfunction "9_9") (pintype "passive"))
    )
    (net (code "40") (name "/SPI_CS3") (class "Default")
      (node (ref "X2") (pin "10") (pinfunction "10_10") (pintype "passive"))
      (node (ref "X8") (pin "1") (pinfunction "1_1") (pintype "passive"))
    )
    (net (code "41") (name "/SPI_CS4") (class "Default")
      (node (ref "X2") (pin "11") (pinfunction "11_11") (pintype "passive"))
      (node (ref "X6") (pin "1") (pinfunction "1_1") (pintype "passive"))
    )
    (net (code "42") (name "/SPI_MISO") (class "Default")
      (node (ref "X16") (pin "1") (pinfunction "1_1") (pintype "passive"))
      (node (ref "X2") (pin "6") (pinfunction "6_6") (pintype "passive"))
    )
    (net (code "43") (name "/SPI_MOSI") (class "Default")
      (node (ref "X18") (pin "1") (pinfunction "1_1") (pintype "passive"))
      (node (ref "X2") (pin "5") (pinfunction "5_5") (pintype "passive"))
    )
    (net (code "44") (name "/SWCLK") (class "Default")
      (node (ref "X25") (pin "1") (pinfunction "1_1") (pintype "passive"))
      (node (ref "X45") (pin "4") (pinfunction "4_4") (pintype "passive"))
    )
    (net (code "45") (name "/SWDIO") (class "Default")
      (node (ref "X25") (pin "2") (pinfunction "2_2") (pintype "passive"))
      (node (ref "X45") (pin "2") (pinfunction "2_2") (pintype "passive"))
    )
    (net (code "46") (name "/SWO") (class "Default")
      (node (ref "X45") (pin "6") (pinfunction "6_6") (pintype "passive"))
    )
    (net (code "47") (name "/TXD_CP2102") (class "Default")
      (node (ref "IC1") (pin "18") (pinfunction "TXD_18") (pintype "passive"))
      (node (ref "R19") (pin "1") (pinfunction "1_1") (pintype "passive"))
    )
    (net (code "48") (name "/UART1_CTS") (class "Default")
      (node (ref "X1") (pin "9") (pinfunction "9_9") (pintype "passive"))
      (node (ref "X9") (pin "1") (pinfunction "1_1") (pintype "passive"))
    )
    (net (code "49") (name "/UART1_RTS") (class "Default")
      (node (ref "X1") (pin "10") (pinfunction "10_10") (pintype "passive"))
      (node (ref "X7") (pin "1") (pinfunction "1_1") (pintype "passive"))
    )
    (net (code "50") (name "/UART1_RX") (class "Default")
      (node (ref "R19") (pin "2") (pinfunction "2_2") (pintype "passive"))
      (node (ref "X1") (pin "12") (pinfunction "12_12") (pintype "passive"))
      (node (ref "X3") (pin "1") (pinfunction "1_1") (pintype "passive"))
    )
    (net (code "51") (name "/UART1_TX") (class "Default")
      (node (ref "R18") (pin "2") (pinfunction "2_2") (pintype "passive"))
      (node (ref "X1") (pin "11") (pinfunction "11_11") (pintype "passive"))
      (node (ref "X5") (pin "1") (pinfunction "1_1") (pintype "passive"))
    )
    (net (code "52") (name "/UART2_RX") (class "Default")
      (node (ref "X1") (pin "8") (pinfunction "8_8") (pintype "passive"))
      (node (ref "X11") (pin "1") (pinfunction "1_1") (pintype "passive"))
    )
    (net (code "53") (name "/UART2_TX") (class "Default")
      (node (ref "X1") (pin "7") (pinfunction "7_7") (pintype "passive"))
      (node (ref "X13") (pin "1") (pinfunction "1_1") (pintype "passive"))
    )
    (net (code "54") (name "/USB_0_D1_N") (class "Default")
      (node (ref "R22") (pin "2") (pinfunction "2_2") (pintype "passive"))
      (node (ref "X1") (pin "2") (pinfunction "2_2") (pintype "passive"))
    )
    (net (code "55") (name "/USB_0_D1_P") (class "Default")
      (node (ref "R23") (pin "2") (pinfunction "2_2") (pintype "passive"))
      (node (ref "X1") (pin "1") (pinfunction "1_1") (pintype "passive"))
    )
    (net (code "56") (name "/USB_0_D_N") (class "Default")
      (node (ref "D6") (pin "1") (pinfunction "D1+_1") (pintype "passive"))
      (node (ref "D6") (pin "10") (pinfunction "NC_10") (pintype "passive"))
      (node (ref "R22") (pin "1") (pinfunction "1_1") (pintype "passive"))
      (node (ref "X44") (pin "2") (pinfunction "D-_2") (pintype "passive"))
    )
    (net (code "57") (name "/USB_0_D_P") (class "Default")
      (node (ref "D6") (pin "2") (pinfunction "D1-_2") (pintype "passive"))
      (node (ref "D6") (pin "9") (pinfunction "NC_9") (pintype "passive"))
      (node (ref "R23") (pin "1") (pinfunction "1_1") (pintype "passive"))
      (node (ref "X44") (pin "3") (pinfunction "D+_3") (pintype "passive"))
    )
    (net (code "58") (name "/VBUS_CP2102") (class "Default")
      (node (ref "IC1") (pin "8") (pinfunction "VBUS_8") (pintype "passive"))
      (node (ref "R16") (pin "1") (pinfunction "1_1") (pintype "passive"))
      (node (ref "R17") (pin "2") (pinfunction "2_2") (pintype "passive"))
    )
    (net (code "59") (name "/VDD_CP2102") (class "Default")
      (node (ref "C11") (pin "2") (pinfunction "2_2") (pintype "passive"))
      (node (ref "C12") (pin "2") (pinfunction "2_2") (pintype "passive"))
      (node (ref "IC1") (pin "6") (pinfunction "VDD_6") (pintype "passive"))
      (node (ref "R15") (pin "1") (pinfunction "1_1") (pintype "passive"))
    )
    (net (code "60") (name "/nRESET") (class "Default")
      (node (ref "S5") (pin "1") (pinfunction "1_1") (pintype "passive"))
      (node (ref "S5") (pin "2") (pinfunction "2_2") (pintype "passive"))
      (node (ref "X33") (pin "2") (pinfunction "2_2") (pintype "passive"))
      (node (ref "X45") (pin "10") (pinfunction "10_10") (pintype "passive"))
    )
    (net (code "61") (name "/nRST_CP2102") (class "Default")
      (node (ref "IC1") (pin "9") (pinfunction "~{RST}_9") (pintype "passive"))
      (node (ref "R15") (pin "2") (pinfunction "2_2") (pintype "passive"))
    )
    (net (code "62") (name "3V3") (class "Default")
      (node (ref "C6") (pin "1") (pinfunction "1_1") (pintype "passive"))
      (node (ref "C9") (pin "1") (pinfunction "1_1") (pintype "passive"))
      (node (ref "L1") (pin "1") (pinfunction "1_1") (pintype "passive"))
      (node (ref "R1") (pin "2") (pinfunction "2_2") (pintype "passive"))
      (node (ref "R10") (pin "1") (pinfunction "1_1") (pintype "passive"))
      (node (ref "R14") (pin "2") (pinfunction "2_2") (pintype "passive"))
      (node (ref "R2") (pin "2") (pinfunction "2_2") (pintype "passive"))
      (node (ref "R8") (pin "2") (pinfunction "2_2") (pintype "passive"))
      (node (ref "VR1") (pin "2") (pinfunction "Vout_2") (pintype "passive"))
      (node (ref "X33") (pin "5") (pinfunction "5_5") (pintype "passive"))
      (node (ref "X41") (pin "1") (pinfunction "1_1") (pintype "passive"))
      (node (ref "X42") (pin "1") (pinfunction "1_1") (pintype "passive"))
      (node (ref "X45") (pin "1") (pinfunction "1_1") (pintype "passive"))
      (node (ref "X49") (pin "1") (pinfunction "1_1") (pintype "passive"))
      (node (ref "X50") (pin "1") (pinfunction "1_1") (pintype "passive"))
      (node (ref "X51") (pin "1") (pinfunction "1_1") (pintype "passive"))
    )
    (net (code "63") (name "3V3A") (class "Default")
      (node (ref "C10") (pin "1") (pinfunction "1_1") (pintype "passive"))
      (node (ref "L1") (pin "2") (pinfunction "2_2") (pintype "passive"))
      (node (ref "R13") (pin "3") (pinfunction "3_3") (pintype "passive"))
      (node (ref "R6") (pin "3") (pinfunction "3_3") (pintype "passive"))
      (node (ref "X33") (pin "4") (pinfunction "4_4") (pintype "passive"))
      (node (ref "X41") (pin "2") (pinfunction "2_2") (pintype "passive"))
      (node (ref "X48") (pin "1") (pinfunction "1_1") (pintype "passive"))
    )
    (net (code "64") (name "5V0") (class "Default")
      (node (ref "C5") (pin "1") (pinfunction "1_1") (pintype "passive"))
      (node (ref "D10") (pin "2") (pinfunction "K_2") (pintype "passive"))
      (node (ref "D8") (pin "2") (pinfunction "K_2") (pintype "passive"))
      (node (ref "D9") (pin "2") (pinfunction "K_2") (pintype "passive"))
      (node (ref "R24") (pin "1") (pinfunction "1_1") (pintype "passive"))
      (node (ref "VR1") (pin "3") (pinfunction "Vin_3") (pintype "passive"))
    )
    (net (code "65") (name "GND") (class "Default")
      (node (ref "C1") (pin "2") (pinfunction "2_2") (pintype "passive"))
      (node (ref "C10") (pin "2") (pinfunction "2_2") (pintype "passive"))
      (node (ref "C11") (pin "1") (pinfunction "1_1") (pintype "passive"))
      (node (ref "C12") (pin "1") (pinfunction "1_1") (pintype "passive"))
      (node (ref "C13") (pin "1") (pinfunction "1_1") (pintype "passive"))
      (node (ref "C14") (pin "1") (pinfunction "1_1") (pintype "passive"))
      (node (ref "C2") (pin "2") (pinfunction "2_2") (pintype "passive"))
      (node (ref "C3") (pin "2") (pinfunction "2_2") (pintype "passive"))
      (node (ref "C4") (pin "2") (pinfunction "2_2") (pintype "passive"))
      (node (ref "C5") (pin "2") (pinfunction "2_2") (pintype "passive"))
      (node (ref "C6") (pin "2") (pinfunction "2_2") (pintype "passive"))
      (node (ref "C7") (pin "2") (pinfunction "2_2") (pintype "passive"))
      (node (ref "C8") (pin "2") (pinfunction "2_2") (pintype "passive"))
      (node (ref "C9") (pin "2") (pinfunction "2_2") (pintype "passive"))
      (node (ref "D5") (pin "K") (pinfunction "K_K") (pintype "passive"))
      (node (ref "D6") (pin "3") (pinfunction "GND_3") (pintype "power_in"))
      (node (ref "D6") (pin "8") (pinfunction "GND_8") (pintype "power_in"))
      (node (ref "D7") (pin "3") (pinfunction "GND_3") (pintype "power_in"))
      (node (ref "D7") (pin "8") (pinfunction "GND_8") (pintype "power_in"))
      (node (ref "IC1") (pin "12") (pinfunction "GND_12") (pintype "passive"))
      (node (ref "IC1") (pin "21") (pinfunction "GND_21") (pintype "passive"))
      (node (ref "IC1") (pin "3") (pinfunction "GND_3") (pintype "passive"))
      (node (ref "R13") (pin "1") (pinfunction "1_1") (pintype "passive"))
      (node (ref "R16") (pin "2") (pinfunction "2_2") (pintype "passive"))
      (node (ref "R3") (pin "1") (pinfunction "1_1") (pintype "passive"))
      (node (ref "R4") (pin "1") (pinfunction "1_1") (pintype "passive"))
      (node (ref "R6") (pin "1") (pinfunction "1_1") (pintype "passive"))
      (node (ref "R7") (pin "1") (pinfunction "1_1") (pintype "passive"))
      (node (ref "R9") (pin "1") (pinfunction "1_1") (pintype "passive"))
      (node (ref "S1") (pin "3") (pinfunction "3_3") (pintype "passive"))
      (node (ref "S1") (pin "4") (pinfunction "4_4") (pintype "passive"))
      (node (ref "S2") (pin "3") (pinfunction "3_3") (pintype "passive"))
      (node (ref "S2") (pin "4") (pinfunction "4_4") (pintype "passive"))
      (node (ref "S3") (pin "3") (pinfunction "3_3") (pintype "passive"))
      (node (ref "S3") (pin "4") (pinfunction "4_4") (pintype "passive"))
      (node (ref "S4") (pin "3") (pinfunction "3_3") (pintype "passive"))
      (node (ref "S4") (pin "4") (pinfunction "4_4") (pintype "passive"))
      (node (ref "S5") (pin "3") (pinfunction "3_3") (pintype "passive"))
      (node (ref "S5") (pin "4") (pinfunction "4_4") (pintype "passive"))
      (node (ref "VR1") (pin "1") (pinfunction "GND_1") (pintype "passive"))
      (node (ref "X33") (pin "1") (pinfunction "1_1") (pintype "passive"))
      (node (ref "X33") (pin "3") (pinfunction "3_3") (pintype "passive"))
      (node (ref "X44") (pin "4") (pinfunction "ID_4") (pintype "passive"))
      (node (ref "X44") (pin "5") (pinfunction "GND_5") (pintype "power_in"))
      (node (ref "X44") (pin "6") (pinfunction "Shield_6") (pintype "power_in"))
      (node (ref "X45") (pin "3") (pinfunction "3_3") (pintype "passive"))
      (node (ref "X45") (pin "5") (pinfunction "5_5") (pintype "passive"))
      (node (ref "X45") (pin "9") (pinfunction "9_9") (pintype "passive"))
      (node (ref "X46") (pin "4") (pinfunction "ID_4") (pintype "passive"))
      (node (ref "X46") (pin "5") (pinfunction "GND_5") (pintype "power_in"))
      (node (ref "X46") (pin "6") (pinfunction "Shield_6") (pintype "power_in"))
      (node (ref "X47") (pin "2") (pinfunction "2_2") (pintype "passive"))
      (node (ref "X52") (pin "1") (pinfunction "1_1") (pintype "passive"))
      (node (ref "X53") (pin "1") (pinfunction "1_1") (pintype "passive"))
      (node (ref "X54") (pin "1") (pinfunction "1_1") (pintype "passive"))
      (node (ref "X55") (pin "1") (pinfunction "1_1") (pintype "passive"))
      (node (ref "X56") (pin "1") (pinfunction "1_1") (pintype "passive"))
      (node (ref "X57") (pin "1") (pinfunction "1_1") (pintype "passive"))
      (node (ref "X58") (pin "1") (pinfunction "1_1") (pintype "passive"))
      (node (ref "X59") (pin "1") (pinfunction "1_1") (pintype "passive"))
      (node (ref "X60") (pin "1") (pinfunction "1_1") (pintype "passive"))
      (node (ref "X61") (pin "1") (pinfunction "1_1") (pintype "passive"))
      (node (ref "X62") (pin "1") (pinfunction "1_1") (pintype "passive"))
      (node (ref "X63") (pin "1") (pinfunction "1_1") (pintype "passive"))
      (node (ref "X64") (pin "1") (pinfunction "1_1") (pintype "passive"))
      (node (ref "X65") (pin "1") (pinfunction "1_1") (pintype "passive"))
    )
    (net (code "66") (name "Net-(C3-Pad1)") (class "Default")
      (node (ref "C3") (pin "1") (pinfunction "1_1") (pintype "passive"))
      (node (ref "R20") (pin "1") (pinfunction "1_1") (pintype "passive"))
      (node (ref "R5") (pin "1") (pinfunction "1_1") (pintype "passive"))
    )
    (net (code "67") (name "Net-(C7-Pad1)") (class "Default")
      (node (ref "C7") (pin "1") (pinfunction "1_1") (pintype "passive"))
      (node (ref "R12") (pin "1") (pinfunction "1_1") (pintype "passive"))
      (node (ref "R21") (pin "1") (pinfunction "1_1") (pintype "passive"))
    )
    (net (code "68") (name "Net-(D1-PadK)") (class "Default")
      (node (ref "D1") (pin "K") (pinfunction "K_K") (pintype "passive"))
      (node (ref "R3") (pin "2") (pinfunction "2_2") (pintype "passive"))
    )
    (net (code "69") (name "Net-(D2-PadK)") (class "Default")
      (node (ref "D2") (pin "K") (pinfunction "K_K") (pintype "passive"))
      (node (ref "R4") (pin "2") (pinfunction "2_2") (pintype "passive"))
    )
    (net (code "70") (name "Net-(D3-PadK)") (class "Default")
      (node (ref "D3") (pin "K") (pinfunction "K_K") (pintype "passive"))
      (node (ref "R7") (pin "2") (pinfunction "2_2") (pintype "passive"))
    )
    (net (code "71") (name "Net-(D4-PadK)") (class "Default")
      (node (ref "D4") (pin "K") (pinfunction "K_K") (pintype "passive"))
      (node (ref "R9") (pin "2") (pinfunction "2_2") (pintype "passive"))
    )
    (net (code "72") (name "Net-(D5-PadA)") (class "Default")
      (node (ref "D5") (pin "A") (pinfunction "A_A") (pintype "passive"))
      (node (ref "R10") (pin "2") (pinfunction "2_2") (pintype "passive"))
    )
    (net (code "73") (name "Net-(D8-A)") (class "Default")
      (node (ref "D8") (pin "1") (pinfunction "A_1") (pintype "passive"))
      (node (ref "X43") (pin "1") (pinfunction "1_1") (pintype "passive"))
    )
    (net (code "74") (name "Net-(D9-A)") (class "Default")
      (node (ref "D9") (pin "1") (pinfunction "A_1") (pintype "passive"))
      (node (ref "X66") (pin "1") (pinfunction "1_1") (pintype "passive"))
    )
    (net (code "75") (name "Net-(D10-A)") (class "Default")
      (node (ref "D10") (pin "1") (pinfunction "A_1") (pintype "passive"))
      (node (ref "R24") (pin "2") (pinfunction "2_2") (pintype "passive"))
      (node (ref "X47") (pin "1") (pinfunction "1_1") (pintype "passive"))
    )
    (net (code "76") (name "Net-(L2-Pad1)") (class "Default")
      (node (ref "L2") (pin "1") (pinfunction "1_1") (pintype "passive"))
      (node (ref "X43") (pin "2") (pinfunction "2_2") (pintype "passive"))
    )
    (net (code "77") (name "Net-(R5-Pad2)") (class "Default")
      (node (ref "R5") (pin "2") (pinfunction "2_2") (pintype "passive"))
      (node (ref "R6") (pin "2") (pinfunction "2_2") (pintype "passive"))
    )
    (net (code "78") (name "Net-(R12-Pad2)") (class "Default")
      (node (ref "R12") (pin "2") (pinfunction "2_2") (pintype "passive"))
      (node (ref "R13") (pin "2") (pinfunction "2_2") (pintype "passive"))
    )
    (net (code "79") (name "Net-(X44-VBUS)") (class "Default")
      (node (ref "L2") (pin "2") (pinfunction "2_2") (pintype "passive"))
      (node (ref "X44") (pin "1") (pinfunction "VBUS_1") (pintype "power_in"))
    )
    (net (code "80") (name "Net-(X46-VBUS)") (class "Default")
      (node (ref "L3") (pin "2") (pinfunction "2_2") (pintype "passive"))
      (node (ref "X46") (pin "1") (pinfunction "VBUS_1") (pintype "power_in"))
    )
    (net (code "81") (name "VBUS") (class "Default")
      (node (ref "C13") (pin "2") (pinfunction "2_2") (pintype "passive"))
      (node (ref "C14") (pin "2") (pinfunction "2_2") (pintype "passive"))
      (node (ref "IC1") (pin "7") (pinfunction "VREGIN_7") (pintype "passive"))
      (node (ref "L3") (pin "1") (pinfunction "1_1") (pintype "passive"))
      (node (ref "R17") (pin "1") (pinfunction "1_1") (pintype "passive"))
      (node (ref "X66") (pin "2") (pinfunction "2_2") (pintype "passive"))
    )
    (net (code "82") (name "unconnected-(D6-D2+-Pad4)") (class "Default")
      (node (ref "D6") (pin "4") (pinfunction "D2+_4") (pintype "passive+no_connect"))
    )
    (net (code "83") (name "unconnected-(D6-D2--Pad5)") (class "Default")
      (node (ref "D6") (pin "5") (pinfunction "D2-_5") (pintype "passive+no_connect"))
    )
    (net (code "84") (name "unconnected-(D6-NC-Pad6)") (class "Default")
      (node (ref "D6") (pin "6") (pinfunction "NC_6") (pintype "passive+no_connect"))
    )
    (net (code "85") (name "unconnected-(D6-NC-Pad7)") (class "Default")
      (node (ref "D6") (pin "7") (pinfunction "NC_7") (pintype "passive+no_connect"))
    )
    (net (code "86") (name "unconnected-(D7-D2+-Pad4)") (class "Default")
      (node (ref "D7") (pin "4") (pinfunction "D2+_4") (pintype "passive+no_connect"))
    )
    (net (code "87") (name "unconnected-(D7-D2--Pad5)") (class "Default")
      (node (ref "D7") (pin "5") (pinfunction "D2-_5") (pintype "passive+no_connect"))
    )
    (net (code "88") (name "unconnected-(D7-NC-Pad6)") (class "Default")
      (node (ref "D7") (pin "6") (pinfunction "NC_6") (pintype "passive+no_connect"))
    )
    (net (code "89") (name "unconnected-(D7-NC-Pad7)") (class "Default")
      (node (ref "D7") (pin "7") (pinfunction "NC_7") (pintype "passive+no_connect"))
    )
  )
)
